# power.net
KiCad netlist of a schematic drawn in Altium Designer
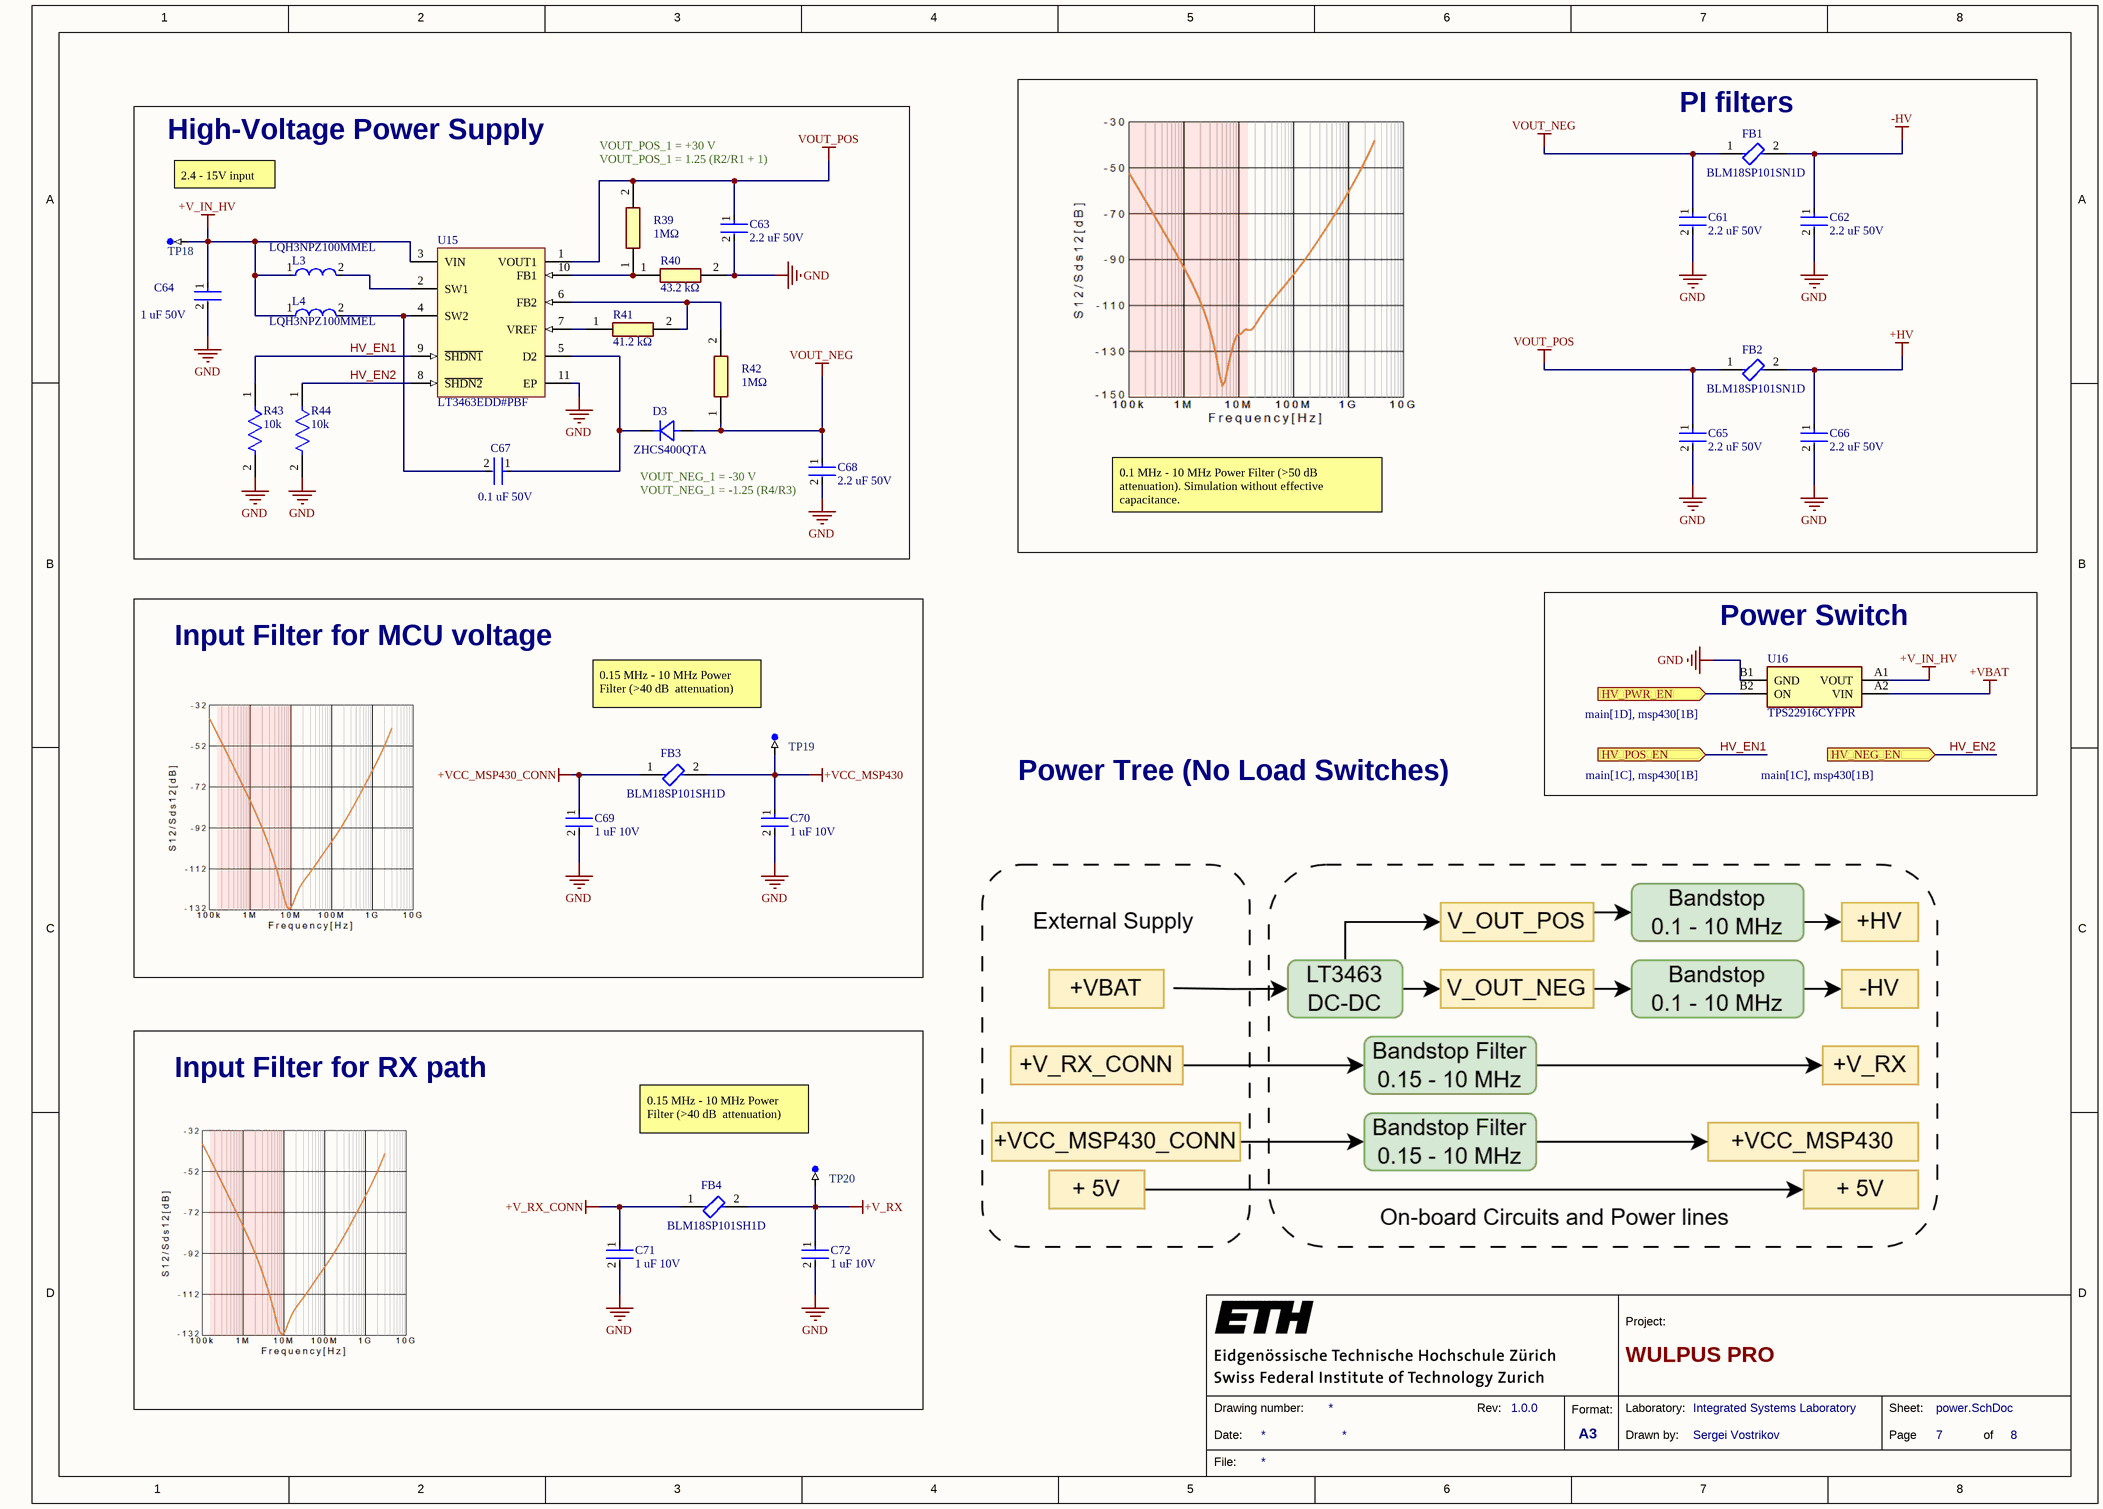
[diagram p0: power.SchDoc]

(export (version "E")
  (design (tool "Eeschema 10.0.6"))
  (components
    (comp (ref "C61")
      (value "2.2 uF 50V")
      (footprint "FP-GRM188-0_2-IPC_B")
      (description "GRM188R61H225ME11D")
      (fields (field (name "TOLERANCE") "20%"))
      (libsource (lib "Altium Content Vault") (part "11868f565c42a9108669ba33697ecf6"))
    )
    (comp (ref "C62")
      (value "2.2 uF 50V")
      (footprint "FP-GRM188-0_2-IPC_B")
      (description "GRM188R61H225ME11D")
      (fields (field (name "TOLERANCE") "20%"))
      (libsource (lib "Altium Content Vault") (part "11868f565c42a9108669ba33697ecf6"))
    )
    (comp (ref "C63")
      (value "2.2 uF 50V")
      (footprint "FP-GRM188-0_2-IPC_B")
      (description "GRM188R61H225ME11D")
      (fields (field (name "TOLERANCE") "20%"))
      (libsource (lib "Altium Content Vault") (part "11868f565c42a9108669ba33697ecf6"))
    )
    (comp (ref "C64")
      (value "1 uF 50V")
      (footprint "FP-GCM21B-0_15-IPC_C")
      (description "GCM21BR71H105KA03L")
      (fields (field (name "TOLERANCE") "10%"))
      (libsource (lib "Altium Content Vault") (part "02cd4be3c70576c341d710602a673aa"))
    )
    (comp (ref "C65")
      (value "2.2 uF 50V")
      (footprint "FP-GRM188-0_2-IPC_B")
      (description "GRM188R61H225ME11D")
      (fields (field (name "TOLERANCE") "20%"))
      (libsource (lib "Altium Content Vault") (part "11868f565c42a9108669ba33697ecf6"))
    )
    (comp (ref "C66")
      (value "2.2 uF 50V")
      (footprint "FP-GRM188-0_2-IPC_B")
      (description "GRM188R61H225ME11D")
      (fields (field (name "TOLERANCE") "20%"))
      (libsource (lib "Altium Content Vault") (part "11868f565c42a9108669ba33697ecf6"))
    )
    (comp (ref "C67")
      (value "0.1 uF 50V")
      (footprint "FP-GRM155-0_05-MFG")
      (description "GRM155C71H104KE19D")
      (fields (field (name "TOLERANCE") "10%"))
      (libsource (lib "Altium Content Vault") (part "02cd4be3c70576c341d710602a673aa"))
    )
    (comp (ref "C68")
      (value "2.2 uF 50V")
      (footprint "FP-GRM188-0_2-IPC_B")
      (description "GRM188R61H225ME11D")
      (fields (field (name "TOLERANCE") "20%"))
      (libsource (lib "Altium Content Vault") (part "11868f565c42a9108669ba33697ecf6"))
    )
    (comp (ref "C69")
      (value "1 uF 10V")
      (footprint "FP-GRM155-0_1-IPC_C")
      (description "GRM155Z71A105KE01D")
      (libsource (lib "Altium Content Vault") (part "11868f565c42a9108669ba33697ecf6"))
    )
    (comp (ref "C70")
      (value "1 uF 10V")
      (footprint "FP-GRM155-0_1-IPC_C")
      (description "GRM155Z71A105KE01D")
      (libsource (lib "Altium Content Vault") (part "11868f565c42a9108669ba33697ecf6"))
    )
    (comp (ref "C71")
      (value "1 uF 10V")
      (footprint "FP-GRM155-0_1-IPC_C")
      (description "GRM155Z71A105KE01D")
      (libsource (lib "Altium Content Vault") (part "11868f565c42a9108669ba33697ecf6"))
    )
    (comp (ref "C72")
      (value "1 uF 10V")
      (footprint "FP-GRM155-0_1-IPC_C")
      (description "GRM155Z71A105KE01D")
      (libsource (lib "Altium Content Vault") (part "11868f565c42a9108669ba33697ecf6"))
    )
    (comp (ref "D3")
      (value "ZHCS400QTA")
      (footprint "DIODE_SOD323_DIO")
      (description "Diode Schottky 40V 1A Automotive 2-Pin SOD-323 T/R")
      (fields (field (name "MANUFACTURER") "Diodes"))
      (libsource (lib "Schlib1") (part "ZHCS400QTA"))
    )
    (comp (ref "FB1")
      (value "BLM18SP101SN1D")
      (footprint "FP-BLM18-0_15-t0_8-MFG")
      (description "BLM18SP101SN1D Ferrite Bead, 100 Ohm, 3.7A, 0603 Rohs Compliant: Yes")
      (fields (field (name "TOLERANCE") "25%"))
      (libsource (lib "Altium Content Vault") (part "5f30dd21d616792df468990f7003faa"))
    )
    (comp (ref "FB2")
      (value "BLM18SP101SN1D")
      (footprint "FP-BLM18-0_15-t0_8-MFG")
      (description "BLM18SP101SN1D Ferrite Bead, 100 Ohm, 3.7A, 0603 Rohs Compliant: Yes")
      (fields (field (name "TOLERANCE") "25%"))
      (libsource (lib "Altium Content Vault") (part "5f30dd21d616792df468990f7003faa"))
    )
    (comp (ref "FB3")
      (value "BLM18SP101SH1D")
      (footprint "FP-BLM18-0_15-t0_8-MFG")
      (description "BLM18SP101SH1D Ferrite Beads Multi-Layer 100Ohm 25% 100MHz 3.7A 0.022Ohm DCR 0603 Automotive T/R")
      (fields (field (name "TOLERANCE") "25%"))
      (libsource (lib "Altium Content Vault") (part "5f30dd21d616792df468990f7003faa"))
    )
    (comp (ref "FB4")
      (value "BLM18SP101SH1D")
      (footprint "FP-BLM18-0_15-t0_8-MFG")
      (description "BLM18SP101SH1D Ferrite Beads Multi-Layer 100Ohm 25% 100MHz 3.7A 0.022Ohm DCR 0603 Automotive T/R")
      (fields (field (name "TOLERANCE") "25%"))
      (libsource (lib "Altium Content Vault") (part "5f30dd21d616792df468990f7003faa"))
    )
    (comp (ref "L3")
      (value "LQH3NPZ100MMEL")
      (footprint "FP-LQH3NPH_ME-MFG")
      (description "Wire Wound Ferrite Inductor for Power Lines For Automotive 10μH ±20% 0.228Ω 1280mA 1212")
      (fields (field (name "TOLERANCE") "20%"))
      (libsource (lib "Altium Content Vault") (part "725321dda6339637d4d059423bc1c3c"))
    )
    (comp (ref "L4")
      (value "LQH3NPZ100MMEL")
      (footprint "FP-LQH3NPH_ME-MFG")
      (description "Wire Wound Ferrite Inductor for Power Lines For Automotive 10μH ±20% 0.228Ω 1280mA 1212")
      (fields (field (name "TOLERANCE") "20%"))
      (libsource (lib "Altium Content Vault") (part "725321dda6339637d4d059423bc1c3c"))
    )
    (comp (ref "R39")
      (value "1MΩ")
      (footprint "SamacSys:ERJ2RKD1004X")
      (description "ERJ-2RKF1004X")
      (fields (field (name "MOUSER PART NUMBER") "667-ERJ-2RKF1004X"))
      (libsource (lib "*") (part "ERJ-2RKF1004X"))
    )
    (comp (ref "R40")
      (value "43.2 kΩ")
      (footprint "SamacSys:ERJ2RKD1004X")
      (description "ERJ-2RKF4322X")
      (fields (field (name "MOUSER PART NUMBER") "667-ERJ-2RKF4322X"))
      (libsource (lib "SamacSys") (part "ERJ-2RKF4322X"))
    )
    (comp (ref "R41")
      (value "41.2 kΩ")
      (footprint "SamacSys:ERJ2RKD1004X")
      (description "ERJ-2RKF4122X")
      (fields (field (name "MOUSER PART NUMBER") "667-ERJ-2RKF4122X"))
      (libsource (lib "SamacSys") (part "ERJ-2RKF4122X"))
    )
    (comp (ref "R42")
      (value "1MΩ")
      (footprint "SamacSys:ERJ2RKD1004X")
      (description "ERJ-2RKF1004X")
      (fields (field (name "MOUSER PART NUMBER") "667-ERJ-2RKF1004X"))
      (libsource (lib "*") (part "ERJ-2RKF1004X"))
    )
    (comp (ref "R43")
      (value "10k")
      (footprint "FP-CRCW0402-e3-IPC_B")
      (description "CRCW040210K0JNED")
      (fields (field (name "TOLERANCE") "5%"))
      (libsource (lib "Altium Content Vault") (part "1029c3af85768c4190bb7ad29bc67b5"))
    )
    (comp (ref "R44")
      (value "10k")
      (footprint "FP-CRCW0402-e3-IPC_B")
      (description "CRCW040210K0JNED")
      (fields (field (name "TOLERANCE") "5%"))
      (libsource (lib "Altium Content Vault") (part "1029c3af85768c4190bb7ad29bc67b5"))
    )
    (comp (ref "TP18")
      (value "TP-SM-C-100")
      (footprint "TP-SM-C-100")
      (description "Test Point, Surface Mount, Circular, Pad Diameter 1 mm")
      (libsource (lib "wulpus") (part "CMP-0484-00002-1"))
    )
    (comp (ref "TP19")
      (value "TP-SM-C-100")
      (footprint "TP-SM-C-100")
      (description "Test Point, Surface Mount, Circular, Pad Diameter 1 mm")
      (libsource (lib "wulpus") (part "CMP-0484-00002-1"))
    )
    (comp (ref "TP20")
      (value "TP-SM-C-100")
      (footprint "TP-SM-C-100")
      (description "Test Point, Surface Mount, Circular, Pad Diameter 1 mm")
      (libsource (lib "wulpus") (part "CMP-0484-00002-1"))
    )
    (comp (ref "U15")
      (value "LT3463EDD#PBF")
      (footprint "LT-DD-10_V")
      (fields (field (name "PARTNUMBER") "LT3463AEDD#PBF") (field (name "MANUFACTURER") "Linear Technology"))
      (libsource (lib "Altium Content Vault") (part "LT-LT3463A-DD-10"))
    )
    (comp (ref "U16")
      (value "TPS22916CYFPR")
      (footprint "BGA4C40P2X2_78X78X50")
      (description "TPS22916 5.5-V, 2-A Ultra-Low Leakage Load Switch")
      (libsource (lib "TPS22916CYFPR") (part "TPS22916CYFPR"))
    )
  )
  (nets
    (net (code "1") (name "+HV") (class "Default")
      (node (ref "C66") (pin "1") (pinfunction "1_1") (pintype "passive"))
      (node (ref "FB2") (pin "2") (pinfunction "2_2") (pintype "passive"))
    )
    (net (code "2") (name "+VBAT") (class "Default")
      (node (ref "U16") (pin "A2") (pinfunction "VIN_A2") (pintype "passive"))
    )
    (net (code "3") (name "+VCC_MSP430") (class "Default")
      (node (ref "C70") (pin "1") (pinfunction "1_1") (pintype "passive"))
      (node (ref "FB3") (pin "2") (pinfunction "2_2") (pintype "passive"))
      (node (ref "TP19") (pin "1") (pinfunction "1_1") (pintype "input"))
    )
    (net (code "4") (name "+VCC_MSP430_CONN") (class "Default")
      (node (ref "C69") (pin "1") (pinfunction "1_1") (pintype "passive"))
      (node (ref "FB3") (pin "1") (pinfunction "1_1") (pintype "passive"))
    )
    (net (code "5") (name "+V_IN_HV") (class "Default")
      (node (ref "C64") (pin "1") (pinfunction "1_1") (pintype "passive"))
      (node (ref "L3") (pin "1") (pinfunction "1_1") (pintype "passive"))
      (node (ref "L4") (pin "1") (pinfunction "1_1") (pintype "passive"))
      (node (ref "TP18") (pin "1") (pinfunction "1_1") (pintype "input"))
      (node (ref "U15") (pin "3") (pinfunction "VIN_3") (pintype "power_in"))
      (node (ref "U16") (pin "A1") (pinfunction "VOUT_A1") (pintype "passive"))
    )
    (net (code "6") (name "+V_RX") (class "Default")
      (node (ref "C72") (pin "1") (pinfunction "1_1") (pintype "passive"))
      (node (ref "FB4") (pin "2") (pinfunction "2_2") (pintype "passive"))
      (node (ref "TP20") (pin "1") (pinfunction "1_1") (pintype "input"))
    )
    (net (code "7") (name "+V_RX_CONN") (class "Default")
      (node (ref "C71") (pin "1") (pinfunction "1_1") (pintype "passive"))
      (node (ref "FB4") (pin "1") (pinfunction "1_1") (pintype "passive"))
    )
    (net (code "8") (name "-HV") (class "Default")
      (node (ref "C62") (pin "1") (pinfunction "1_1") (pintype "passive"))
      (node (ref "FB1") (pin "2") (pinfunction "2_2") (pintype "passive"))
    )
    (net (code "9") (name "/HV_EN1") (class "Default")
      (node (ref "R43") (pin "1") (pinfunction "1_1") (pintype "passive"))
      (node (ref "U15") (pin "9") (pinfunction "~{SHDN1}_9") (pintype "input"))
    )
    (net (code "10") (name "/HV_EN2") (class "Default")
      (node (ref "R44") (pin "1") (pinfunction "1_1") (pintype "passive"))
      (node (ref "U15") (pin "8") (pinfunction "~{SHDN2}_8") (pintype "input"))
    )
    (net (code "11") (name "/HV_PWR_EN") (class "Default")
      (node (ref "U16") (pin "B2") (pinfunction "ON_B2") (pintype "passive"))
    )
    (net (code "12") (name "GND") (class "Default")
      (node (ref "C61") (pin "2") (pinfunction "2_2") (pintype "passive"))
      (node (ref "C62") (pin "2") (pinfunction "2_2") (pintype "passive"))
      (node (ref "C63") (pin "2") (pinfunction "2_2") (pintype "passive"))
      (node (ref "C64") (pin "2") (pinfunction "2_2") (pintype "passive"))
      (node (ref "C65") (pin "2") (pinfunction "2_2") (pintype "passive"))
      (node (ref "C66") (pin "2") (pinfunction "2_2") (pintype "passive"))
      (node (ref "C68") (pin "2") (pinfunction "2_2") (pintype "passive"))
      (node (ref "C69") (pin "2") (pinfunction "2_2") (pintype "passive"))
      (node (ref "C70") (pin "2") (pinfunction "2_2") (pintype "passive"))
      (node (ref "C71") (pin "2") (pinfunction "2_2") (pintype "passive"))
      (node (ref "C72") (pin "2") (pinfunction "2_2") (pintype "passive"))
      (node (ref "R40") (pin "2") (pinfunction "2_2") (pintype "passive"))
      (node (ref "R43") (pin "2") (pinfunction "2_2") (pintype "passive"))
      (node (ref "R44") (pin "2") (pinfunction "2_2") (pintype "passive"))
      (node (ref "U15") (pin "11") (pinfunction "EP_11") (pintype "power_in"))
      (node (ref "U16") (pin "B1") (pinfunction "GND_B1") (pintype "passive"))
    )
    (net (code "13") (name "Net-(U15-D2)") (class "Default")
      (node (ref "C67") (pin "1") (pinfunction "1_1") (pintype "passive"))
      (node (ref "D3") (pin "1") (pinfunction "1_1") (pintype "passive"))
      (node (ref "U15") (pin "5") (pinfunction "D2_5") (pintype "passive"))
    )
    (net (code "14") (name "Net-(U15-FB1)") (class "Default")
      (node (ref "R39") (pin "1") (pinfunction "1_1") (pintype "passive"))
      (node (ref "R40") (pin "1") (pinfunction "1_1") (pintype "passive"))
      (node (ref "U15") (pin "10") (pinfunction "FB1_10") (pintype "input"))
    )
    (net (code "15") (name "Net-(U15-FB2)") (class "Default")
      (node (ref "R41") (pin "2") (pinfunction "2_2") (pintype "passive"))
      (node (ref "R42") (pin "2") (pinfunction "2_2") (pintype "passive"))
      (node (ref "U15") (pin "6") (pinfunction "FB2_6") (pintype "input"))
    )
    (net (code "16") (name "Net-(U15-SW1)") (class "Default")
      (node (ref "L3") (pin "2") (pinfunction "2_2") (pintype "passive"))
      (node (ref "U15") (pin "2") (pinfunction "SW1_2") (pintype "passive"))
    )
    (net (code "17") (name "Net-(U15-SW2)") (class "Default")
      (node (ref "C67") (pin "2") (pinfunction "2_2") (pintype "passive"))
      (node (ref "L4") (pin "2") (pinfunction "2_2") (pintype "passive"))
      (node (ref "U15") (pin "4") (pinfunction "SW2_4") (pintype "passive"))
    )
    (net (code "18") (name "Net-(U15-VREF)") (class "Default")
      (node (ref "R41") (pin "1") (pinfunction "1_1") (pintype "passive"))
      (node (ref "U15") (pin "7") (pinfunction "VREF_7") (pintype "input"))
    )
    (net (code "19") (name "VOUT_NEG") (class "Default")
      (node (ref "C61") (pin "1") (pinfunction "1_1") (pintype "passive"))
      (node (ref "C68") (pin "1") (pinfunction "1_1") (pintype "passive"))
      (node (ref "D3") (pin "2") (pinfunction "2_2") (pintype "passive"))
      (node (ref "FB1") (pin "1") (pinfunction "1_1") (pintype "passive"))
      (node (ref "R42") (pin "1") (pinfunction "1_1") (pintype "passive"))
    )
    (net (code "20") (name "VOUT_POS") (class "Default")
      (node (ref "C63") (pin "1") (pinfunction "1_1") (pintype "passive"))
      (node (ref "C65") (pin "1") (pinfunction "1_1") (pintype "passive"))
      (node (ref "FB2") (pin "1") (pinfunction "1_1") (pintype "passive"))
      (node (ref "R39") (pin "2") (pinfunction "2_2") (pintype "passive"))
      (node (ref "U15") (pin "1") (pinfunction "VOUT1_1") (pintype "power_in"))
    )
  )
)
